# ShieldClock.net
KiCad netlist of a schematic drawn in Altium Designer
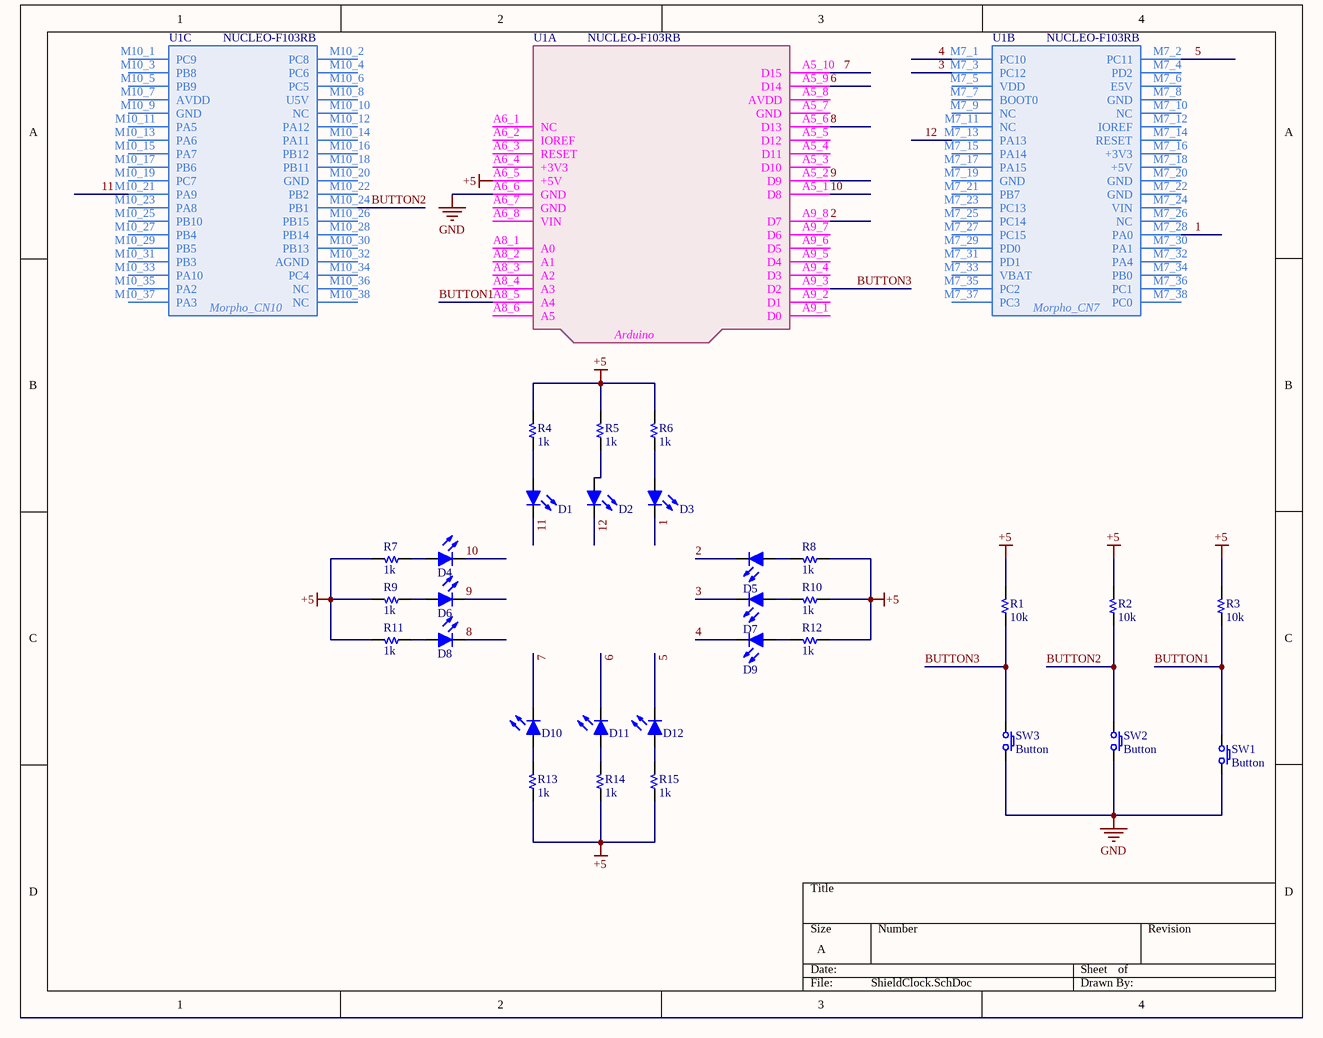
[diagram p0: ShieldClock.SchDoc]

(export (version "E")
  (design (tool "Eeschema 10.0.6"))
  (components
    (comp (ref "D1")
      (value "Led")
      (footprint "LED 3MM - red")
      (description "Typical LED")
      (libsource (lib "chipfc_altium_libs") (part "Led"))
    )
    (comp (ref "D2")
      (value "Led")
      (footprint "LED 3MM - red")
      (description "Typical LED")
      (libsource (lib "chipfc_altium_libs") (part "Led"))
    )
    (comp (ref "D3")
      (value "Led")
      (footprint "LED 3MM - red")
      (description "Typical LED")
      (libsource (lib "chipfc_altium_libs") (part "Led"))
    )
    (comp (ref "D4")
      (value "Led")
      (footprint "LED 3MM - red")
      (description "Typical LED")
      (libsource (lib "chipfc_altium_libs") (part "Led"))
    )
    (comp (ref "D5")
      (value "Led")
      (footprint "LED 3MM - red")
      (description "Typical LED")
      (libsource (lib "chipfc_altium_libs") (part "Led"))
    )
    (comp (ref "D6")
      (value "Led")
      (footprint "LED 3MM - red")
      (description "Typical LED")
      (libsource (lib "chipfc_altium_libs") (part "Led"))
    )
    (comp (ref "D7")
      (value "Led")
      (footprint "LED 3MM - red")
      (description "Typical LED")
      (libsource (lib "chipfc_altium_libs") (part "Led"))
    )
    (comp (ref "D8")
      (value "Led")
      (footprint "LED 3MM - red")
      (description "Typical LED")
      (libsource (lib "chipfc_altium_libs") (part "Led"))
    )
    (comp (ref "D9")
      (value "Led")
      (footprint "LED 3MM - red")
      (description "Typical LED")
      (libsource (lib "chipfc_altium_libs") (part "Led"))
    )
    (comp (ref "D10")
      (value "Led")
      (footprint "LED 3MM - red")
      (description "Typical LED")
      (libsource (lib "chipfc_altium_libs") (part "Led"))
    )
    (comp (ref "D11")
      (value "Led")
      (footprint "LED 3MM - red")
      (description "Typical LED")
      (libsource (lib "chipfc_altium_libs") (part "Led"))
    )
    (comp (ref "D12")
      (value "Led")
      (footprint "LED 3MM - red")
      (description "Typical LED")
      (libsource (lib "chipfc_altium_libs") (part "Led"))
    )
    (comp (ref "R1")
      (value "10k")
      (footprint "R 0805")
      (description "Resistor")
      (libsource (lib "chipfc_altium_libs") (part "Resistor"))
    )
    (comp (ref "R2")
      (value "10k")
      (footprint "R 0805")
      (description "Resistor")
      (libsource (lib "chipfc_altium_libs") (part "Resistor"))
    )
    (comp (ref "R3")
      (value "10k")
      (footprint "R 0805")
      (description "Resistor")
      (libsource (lib "chipfc_altium_libs") (part "Resistor"))
    )
    (comp (ref "R4")
      (value "1k")
      (footprint "R 0805")
      (description "Resistor")
      (libsource (lib "chipfc_altium_libs") (part "Resistor"))
    )
    (comp (ref "R5")
      (value "1k")
      (footprint "R 0805")
      (description "Resistor")
      (libsource (lib "chipfc_altium_libs") (part "Resistor"))
    )
    (comp (ref "R6")
      (value "1k")
      (footprint "R 0805")
      (description "Resistor")
      (libsource (lib "chipfc_altium_libs") (part "Resistor"))
    )
    (comp (ref "R7")
      (value "1k")
      (footprint "R 0805")
      (description "Resistor")
      (libsource (lib "chipfc_altium_libs") (part "Resistor"))
    )
    (comp (ref "R8")
      (value "1k")
      (footprint "R 0805")
      (description "Resistor")
      (libsource (lib "chipfc_altium_libs") (part "Resistor"))
    )
    (comp (ref "R9")
      (value "1k")
      (footprint "R 0805")
      (description "Resistor")
      (libsource (lib "chipfc_altium_libs") (part "Resistor"))
    )
    (comp (ref "R10")
      (value "1k")
      (footprint "R 0805")
      (description "Resistor")
      (libsource (lib "chipfc_altium_libs") (part "Resistor"))
    )
    (comp (ref "R11")
      (value "1k")
      (footprint "R 0805")
      (description "Resistor")
      (libsource (lib "chipfc_altium_libs") (part "Resistor"))
    )
    (comp (ref "R12")
      (value "1k")
      (footprint "R 0805")
      (description "Resistor")
      (libsource (lib "chipfc_altium_libs") (part "Resistor"))
    )
    (comp (ref "R13")
      (value "1k")
      (footprint "R 0805")
      (description "Resistor")
      (libsource (lib "chipfc_altium_libs") (part "Resistor"))
    )
    (comp (ref "R14")
      (value "1k")
      (footprint "R 0805")
      (description "Resistor")
      (libsource (lib "chipfc_altium_libs") (part "Resistor"))
    )
    (comp (ref "R15")
      (value "1k")
      (footprint "R 0805")
      (description "Resistor")
      (libsource (lib "chipfc_altium_libs") (part "Resistor"))
    )
    (comp (ref "SW1")
      (value "Button")
      (footprint "SW/2/DIP")
      (description "Tact switch 2 pin")
      (libsource (lib "chipfc_altium_libs") (part "SW SPST"))
    )
    (comp (ref "SW2")
      (value "Button")
      (footprint "SW/2/DIP")
      (description "Tact switch 2 pin")
      (libsource (lib "chipfc_altium_libs") (part "SW SPST"))
    )
    (comp (ref "SW3")
      (value "Button")
      (footprint "SW/2/DIP")
      (description "Tact switch 2 pin")
      (libsource (lib "chipfc_altium_libs") (part "SW SPST"))
    )
    (comp (ref "U1")
      (value "NUCLEO-F103RB")
      (footprint "NUCLEO")
      (fields (field (name "MANUFACTURER") "STMicroelectronics"))
      (libsource (lib "nucleo") (part "NUCLEO-F103RB"))
    )
  )
  (nets
    (net (code "1") (name "+5") (class "Default")
      (node (ref "R1") (pin "2") (pinfunction "2_2") (pintype "passive"))
      (node (ref "R10") (pin "1") (pinfunction "1_1") (pintype "passive"))
      (node (ref "R11") (pin "2") (pinfunction "2_2") (pintype "passive"))
      (node (ref "R12") (pin "1") (pinfunction "1_1") (pintype "passive"))
      (node (ref "R13") (pin "1") (pinfunction "1_1") (pintype "passive"))
      (node (ref "R14") (pin "1") (pinfunction "1_1") (pintype "passive"))
      (node (ref "R15") (pin "1") (pinfunction "1_1") (pintype "passive"))
      (node (ref "R2") (pin "2") (pinfunction "2_2") (pintype "passive"))
      (node (ref "R3") (pin "2") (pinfunction "2_2") (pintype "passive"))
      (node (ref "R4") (pin "2") (pinfunction "2_2") (pintype "passive"))
      (node (ref "R5") (pin "2") (pinfunction "2_2") (pintype "passive"))
      (node (ref "R6") (pin "2") (pinfunction "2_2") (pintype "passive"))
      (node (ref "R7") (pin "2") (pinfunction "2_2") (pintype "passive"))
      (node (ref "R8") (pin "1") (pinfunction "1_1") (pintype "passive"))
      (node (ref "R9") (pin "2") (pinfunction "2_2") (pintype "passive"))
      (node (ref "U1") (pin "A6_5") (pinfunction "+5V_A6_5") (pintype "passive"))
    )
    (net (code "2") (name "/1") (class "Default")
      (node (ref "D3") (pin "2") (pinfunction "K_2") (pintype "passive"))
      (node (ref "U1") (pin "M7_28") (pinfunction "PA0_M7_28") (pintype "passive"))
    )
    (net (code "3") (name "/2") (class "Default")
      (node (ref "D5") (pin "2") (pinfunction "K_2") (pintype "passive"))
      (node (ref "U1") (pin "A9_8") (pinfunction "D7_A9_8") (pintype "passive"))
    )
    (net (code "4") (name "/3") (class "Default")
      (node (ref "D7") (pin "2") (pinfunction "K_2") (pintype "passive"))
      (node (ref "U1") (pin "M7_3") (pinfunction "PC12_M7_3") (pintype "passive"))
    )
    (net (code "5") (name "/4") (class "Default")
      (node (ref "D9") (pin "2") (pinfunction "K_2") (pintype "passive"))
      (node (ref "U1") (pin "M7_1") (pinfunction "PC10_M7_1") (pintype "passive"))
    )
    (net (code "6") (name "/5") (class "Default")
      (node (ref "D12") (pin "2") (pinfunction "K_2") (pintype "passive"))
      (node (ref "U1") (pin "M7_2") (pinfunction "PC11_M7_2") (pintype "passive"))
    )
    (net (code "7") (name "/6") (class "Default")
      (node (ref "D11") (pin "2") (pinfunction "K_2") (pintype "passive"))
      (node (ref "U1") (pin "A5_9") (pinfunction "D14_A5_9") (pintype "passive"))
    )
    (net (code "8") (name "/7") (class "Default")
      (node (ref "D10") (pin "2") (pinfunction "K_2") (pintype "passive"))
      (node (ref "U1") (pin "A5_10") (pinfunction "D15_A5_10") (pintype "passive"))
    )
    (net (code "9") (name "/8") (class "Default")
      (node (ref "D8") (pin "2") (pinfunction "K_2") (pintype "passive"))
      (node (ref "U1") (pin "A5_6") (pinfunction "D13_A5_6") (pintype "passive"))
    )
    (net (code "10") (name "/9") (class "Default")
      (node (ref "D6") (pin "2") (pinfunction "K_2") (pintype "passive"))
      (node (ref "U1") (pin "A5_2") (pinfunction "D9_A5_2") (pintype "passive"))
    )
    (net (code "11") (name "/10") (class "Default")
      (node (ref "D4") (pin "2") (pinfunction "K_2") (pintype "passive"))
      (node (ref "U1") (pin "A5_1") (pinfunction "D8_A5_1") (pintype "passive"))
    )
    (net (code "12") (name "/11") (class "Default")
      (node (ref "D1") (pin "2") (pinfunction "K_2") (pintype "passive"))
      (node (ref "U1") (pin "M10_21") (pinfunction "PA9_M10_21") (pintype "passive"))
    )
    (net (code "13") (name "/12") (class "Default")
      (node (ref "D2") (pin "2") (pinfunction "K_2") (pintype "passive"))
      (node (ref "U1") (pin "M7_13") (pinfunction "PA13_M7_13") (pintype "passive"))
    )
    (net (code "14") (name "/BUTTON1") (class "Default")
      (node (ref "R3") (pin "1") (pinfunction "1_1") (pintype "passive"))
      (node (ref "SW1") (pin "1") (pinfunction "1_1") (pintype "passive"))
      (node (ref "U1") (pin "A8_5") (pinfunction "A4_A8_5") (pintype "passive"))
    )
    (net (code "15") (name "/BUTTON2") (class "Default")
      (node (ref "R2") (pin "1") (pinfunction "1_1") (pintype "passive"))
      (node (ref "SW2") (pin "1") (pinfunction "1_1") (pintype "passive"))
      (node (ref "U1") (pin "M10_24") (pinfunction "PB1_M10_24") (pintype "passive"))
    )
    (net (code "16") (name "/BUTTON3") (class "Default")
      (node (ref "R1") (pin "1") (pinfunction "1_1") (pintype "passive"))
      (node (ref "SW3") (pin "1") (pinfunction "1_1") (pintype "passive"))
      (node (ref "U1") (pin "A9_3") (pinfunction "D2_A9_3") (pintype "passive"))
    )
    (net (code "17") (name "GND") (class "Default")
      (node (ref "SW1") (pin "2") (pinfunction "2_2") (pintype "passive"))
      (node (ref "SW2") (pin "2") (pinfunction "2_2") (pintype "passive"))
      (node (ref "SW3") (pin "2") (pinfunction "2_2") (pintype "passive"))
      (node (ref "U1") (pin "A6_6") (pinfunction "GND_A6_6") (pintype "passive"))
    )
    (net (code "18") (name "Net-(D1-A)") (class "Default")
      (node (ref "D1") (pin "1") (pinfunction "A_1") (pintype "passive"))
      (node (ref "R4") (pin "1") (pinfunction "1_1") (pintype "passive"))
    )
    (net (code "19") (name "Net-(D2-A)") (class "Default")
      (node (ref "D2") (pin "1") (pinfunction "A_1") (pintype "passive"))
      (node (ref "R5") (pin "1") (pinfunction "1_1") (pintype "passive"))
    )
    (net (code "20") (name "Net-(D3-A)") (class "Default")
      (node (ref "D3") (pin "1") (pinfunction "A_1") (pintype "passive"))
      (node (ref "R6") (pin "1") (pinfunction "1_1") (pintype "passive"))
    )
    (net (code "21") (name "Net-(D4-A)") (class "Default")
      (node (ref "D4") (pin "1") (pinfunction "A_1") (pintype "passive"))
      (node (ref "R7") (pin "1") (pinfunction "1_1") (pintype "passive"))
    )
    (net (code "22") (name "Net-(D5-A)") (class "Default")
      (node (ref "D5") (pin "1") (pinfunction "A_1") (pintype "passive"))
      (node (ref "R8") (pin "2") (pinfunction "2_2") (pintype "passive"))
    )
    (net (code "23") (name "Net-(D6-A)") (class "Default")
      (node (ref "D6") (pin "1") (pinfunction "A_1") (pintype "passive"))
      (node (ref "R9") (pin "1") (pinfunction "1_1") (pintype "passive"))
    )
    (net (code "24") (name "Net-(D7-A)") (class "Default")
      (node (ref "D7") (pin "1") (pinfunction "A_1") (pintype "passive"))
      (node (ref "R10") (pin "2") (pinfunction "2_2") (pintype "passive"))
    )
    (net (code "25") (name "Net-(D8-A)") (class "Default")
      (node (ref "D8") (pin "1") (pinfunction "A_1") (pintype "passive"))
      (node (ref "R11") (pin "1") (pinfunction "1_1") (pintype "passive"))
    )
    (net (code "26") (name "Net-(D9-A)") (class "Default")
      (node (ref "D9") (pin "1") (pinfunction "A_1") (pintype "passive"))
      (node (ref "R12") (pin "2") (pinfunction "2_2") (pintype "passive"))
    )
    (net (code "27") (name "Net-(D10-A)") (class "Default")
      (node (ref "D10") (pin "1") (pinfunction "A_1") (pintype "passive"))
      (node (ref "R13") (pin "2") (pinfunction "2_2") (pintype "passive"))
    )
    (net (code "28") (name "Net-(D11-A)") (class "Default")
      (node (ref "D11") (pin "1") (pinfunction "A_1") (pintype "passive"))
      (node (ref "R14") (pin "2") (pinfunction "2_2") (pintype "passive"))
    )
    (net (code "29") (name "Net-(D12-A)") (class "Default")
      (node (ref "D12") (pin "1") (pinfunction "A_1") (pintype "passive"))
      (node (ref "R15") (pin "2") (pinfunction "2_2") (pintype "passive"))
    )
    (net (code "30") (name "unconnected-(U1A-+3V3-PadA6_4)") (class "Default")
      (node (ref "U1") (pin "A6_4") (pinfunction "+3V3_A6_4") (pintype "passive"))
    )
    (net (code "31") (name "unconnected-(U1A-A0-PadA8_1)") (class "Default")
      (node (ref "U1") (pin "A8_1") (pinfunction "A0_A8_1") (pintype "passive"))
    )
    (net (code "32") (name "unconnected-(U1A-A1-PadA8_2)") (class "Default")
      (node (ref "U1") (pin "A8_2") (pinfunction "A1_A8_2") (pintype "passive"))
    )
    (net (code "33") (name "unconnected-(U1A-A2-PadA8_3)") (class "Default")
      (node (ref "U1") (pin "A8_3") (pinfunction "A2_A8_3") (pintype "passive"))
    )
    (net (code "34") (name "unconnected-(U1A-A3-PadA8_4)") (class "Default")
      (node (ref "U1") (pin "A8_4") (pinfunction "A3_A8_4") (pintype "passive"))
    )
    (net (code "35") (name "unconnected-(U1A-A5-PadA8_6)") (class "Default")
      (node (ref "U1") (pin "A8_6") (pinfunction "A5_A8_6") (pintype "passive"))
    )
    (net (code "36") (name "unconnected-(U1A-AVDD-PadA5_8)") (class "Default")
      (node (ref "U1") (pin "A5_8") (pinfunction "AVDD_A5_8") (pintype "passive"))
    )
    (net (code "37") (name "unconnected-(U1A-D0-PadA9_1)") (class "Default")
      (node (ref "U1") (pin "A9_1") (pinfunction "D0_A9_1") (pintype "passive"))
    )
    (net (code "38") (name "unconnected-(U1A-D1-PadA9_2)") (class "Default")
      (node (ref "U1") (pin "A9_2") (pinfunction "D1_A9_2") (pintype "passive"))
    )
    (net (code "39") (name "unconnected-(U1A-D3-PadA9_4)") (class "Default")
      (node (ref "U1") (pin "A9_4") (pinfunction "D3_A9_4") (pintype "passive"))
    )
    (net (code "40") (name "unconnected-(U1A-D4-PadA9_5)") (class "Default")
      (node (ref "U1") (pin "A9_5") (pinfunction "D4_A9_5") (pintype "passive"))
    )
    (net (code "41") (name "unconnected-(U1A-D5-PadA9_6)") (class "Default")
      (node (ref "U1") (pin "A9_6") (pinfunction "D5_A9_6") (pintype "passive"))
    )
    (net (code "42") (name "unconnected-(U1A-D6-PadA9_7)") (class "Default")
      (node (ref "U1") (pin "A9_7") (pinfunction "D6_A9_7") (pintype "passive"))
    )
    (net (code "43") (name "unconnected-(U1A-D10-PadA5_3)") (class "Default")
      (node (ref "U1") (pin "A5_3") (pinfunction "D10_A5_3") (pintype "passive"))
    )
    (net (code "44") (name "unconnected-(U1A-D11-PadA5_4)") (class "Default")
      (node (ref "U1") (pin "A5_4") (pinfunction "D11_A5_4") (pintype "passive"))
    )
    (net (code "45") (name "unconnected-(U1A-D12-PadA5_5)") (class "Default")
      (node (ref "U1") (pin "A5_5") (pinfunction "D12_A5_5") (pintype "passive"))
    )
    (net (code "46") (name "unconnected-(U1A-GND-PadA5_7)") (class "Default")
      (node (ref "U1") (pin "A5_7") (pinfunction "GND_A5_7") (pintype "passive"))
    )
    (net (code "47") (name "unconnected-(U1A-GND-PadA6_7)") (class "Default")
      (node (ref "U1") (pin "A6_7") (pinfunction "GND_A6_7") (pintype "passive"))
    )
    (net (code "48") (name "unconnected-(U1A-IOREF-PadA6_2)") (class "Default")
      (node (ref "U1") (pin "A6_2") (pinfunction "IOREF_A6_2") (pintype "passive"))
    )
    (net (code "49") (name "unconnected-(U1A-NC-PadA6_1)") (class "Default")
      (node (ref "U1") (pin "A6_1") (pinfunction "NC_A6_1") (pintype "passive"))
    )
    (net (code "50") (name "unconnected-(U1A-RESET-PadA6_3)") (class "Default")
      (node (ref "U1") (pin "A6_3") (pinfunction "RESET_A6_3") (pintype "passive"))
    )
    (net (code "51") (name "unconnected-(U1A-VIN-PadA6_8)") (class "Default")
      (node (ref "U1") (pin "A6_8") (pinfunction "VIN_A6_8") (pintype "passive"))
    )
    (net (code "52") (name "unconnected-(U1B-+3V3-PadM7_16)") (class "Default")
      (node (ref "U1") (pin "M7_16") (pinfunction "+3V3_M7_16") (pintype "passive"))
    )
    (net (code "53") (name "unconnected-(U1B-+5V-PadM7_18)") (class "Default")
      (node (ref "U1") (pin "M7_18") (pinfunction "+5V_M7_18") (pintype "passive"))
    )
    (net (code "54") (name "unconnected-(U1B-BOOT0-PadM7_7)") (class "Default")
      (node (ref "U1") (pin "M7_7") (pinfunction "BOOT0_M7_7") (pintype "passive"))
    )
    (net (code "55") (name "unconnected-(U1B-E5V-PadM7_6)") (class "Default")
      (node (ref "U1") (pin "M7_6") (pinfunction "E5V_M7_6") (pintype "passive"))
    )
    (net (code "56") (name "unconnected-(U1B-GND-PadM7_8)") (class "Default")
      (node (ref "U1") (pin "M7_8") (pinfunction "GND_M7_8") (pintype "passive"))
    )
    (net (code "57") (name "unconnected-(U1B-GND-PadM7_19)") (class "Default")
      (node (ref "U1") (pin "M7_19") (pinfunction "GND_M7_19") (pintype "passive"))
    )
    (net (code "58") (name "unconnected-(U1B-GND-PadM7_20)") (class "Default")
      (node (ref "U1") (pin "M7_20") (pinfunction "GND_M7_20") (pintype "passive"))
    )
    (net (code "59") (name "unconnected-(U1B-GND-PadM7_22)") (class "Default")
      (node (ref "U1") (pin "M7_22") (pinfunction "GND_M7_22") (pintype "passive"))
    )
    (net (code "60") (name "unconnected-(U1B-IOREF-PadM7_12)") (class "Default")
      (node (ref "U1") (pin "M7_12") (pinfunction "IOREF_M7_12") (pintype "passive"))
    )
    (net (code "61") (name "unconnected-(U1B-NC-PadM7_9)") (class "Default")
      (node (ref "U1") (pin "M7_9") (pinfunction "NC_M7_9") (pintype "passive"))
    )
    (net (code "62") (name "unconnected-(U1B-NC-PadM7_10)") (class "Default")
      (node (ref "U1") (pin "M7_10") (pinfunction "NC_M7_10") (pintype "passive"))
    )
    (net (code "63") (name "unconnected-(U1B-NC-PadM7_11)") (class "Default")
      (node (ref "U1") (pin "M7_11") (pinfunction "NC_M7_11") (pintype "passive"))
    )
    (net (code "64") (name "unconnected-(U1B-NC-PadM7_26)") (class "Default")
      (node (ref "U1") (pin "M7_26") (pinfunction "NC_M7_26") (pintype "passive"))
    )
    (net (code "65") (name "unconnected-(U1B-PA1-PadM7_30)") (class "Default")
      (node (ref "U1") (pin "M7_30") (pinfunction "PA1_M7_30") (pintype "passive"))
    )
    (net (code "66") (name "unconnected-(U1B-PA4-PadM7_32)") (class "Default")
      (node (ref "U1") (pin "M7_32") (pinfunction "PA4_M7_32") (pintype "passive"))
    )
    (net (code "67") (name "unconnected-(U1B-PA14-PadM7_15)") (class "Default")
      (node (ref "U1") (pin "M7_15") (pinfunction "PA14_M7_15") (pintype "passive"))
    )
    (net (code "68") (name "unconnected-(U1B-PA15-PadM7_17)") (class "Default")
      (node (ref "U1") (pin "M7_17") (pinfunction "PA15_M7_17") (pintype "passive"))
    )
    (net (code "69") (name "unconnected-(U1B-PB0-PadM7_34)") (class "Default")
      (node (ref "U1") (pin "M7_34") (pinfunction "PB0_M7_34") (pintype "passive"))
    )
    (net (code "70") (name "unconnected-(U1B-PB7-PadM7_21)") (class "Default")
      (node (ref "U1") (pin "M7_21") (pinfunction "PB7_M7_21") (pintype "passive"))
    )
    (net (code "71") (name "unconnected-(U1B-PC0-PadM7_38)") (class "Default")
      (node (ref "U1") (pin "M7_38") (pinfunction "PC0_M7_38") (pintype "passive"))
    )
    (net (code "72") (name "unconnected-(U1B-PC1-PadM7_36)") (class "Default")
      (node (ref "U1") (pin "M7_36") (pinfunction "PC1_M7_36") (pintype "passive"))
    )
    (net (code "73") (name "unconnected-(U1B-PC2-PadM7_35)") (class "Default")
      (node (ref "U1") (pin "M7_35") (pinfunction "PC2_M7_35") (pintype "passive"))
    )
    (net (code "74") (name "unconnected-(U1B-PC3-PadM7_37)") (class "Default")
      (node (ref "U1") (pin "M7_37") (pinfunction "PC3_M7_37") (pintype "passive"))
    )
    (net (code "75") (name "unconnected-(U1B-PC13-PadM7_23)") (class "Default")
      (node (ref "U1") (pin "M7_23") (pinfunction "PC13_M7_23") (pintype "passive"))
    )
    (net (code "76") (name "unconnected-(U1B-PC14-PadM7_25)") (class "Default")
      (node (ref "U1") (pin "M7_25") (pinfunction "PC14_M7_25") (pintype "passive"))
    )
    (net (code "77") (name "unconnected-(U1B-PC15-PadM7_27)") (class "Default")
      (node (ref "U1") (pin "M7_27") (pinfunction "PC15_M7_27") (pintype "passive"))
    )
    (net (code "78") (name "unconnected-(U1B-PD0-PadM7_29)") (class "Default")
      (node (ref "U1") (pin "M7_29") (pinfunction "PD0_M7_29") (pintype "passive"))
    )
    (net (code "79") (name "unconnected-(U1B-PD1-PadM7_31)") (class "Default")
      (node (ref "U1") (pin "M7_31") (pinfunction "PD1_M7_31") (pintype "passive"))
    )
    (net (code "80") (name "unconnected-(U1B-PD2-PadM7_4)") (class "Default")
      (node (ref "U1") (pin "M7_4") (pinfunction "PD2_M7_4") (pintype "passive"))
    )
    (net (code "81") (name "unconnected-(U1B-RESET-PadM7_14)") (class "Default")
      (node (ref "U1") (pin "M7_14") (pinfunction "RESET_M7_14") (pintype "passive"))
    )
    (net (code "82") (name "unconnected-(U1B-VBAT-PadM7_33)") (class "Default")
      (node (ref "U1") (pin "M7_33") (pinfunction "VBAT_M7_33") (pintype "passive"))
    )
    (net (code "83") (name "unconnected-(U1B-VDD-PadM7_5)") (class "Default")
      (node (ref "U1") (pin "M7_5") (pinfunction "VDD_M7_5") (pintype "passive"))
    )
    (net (code "84") (name "unconnected-(U1B-VIN-PadM7_24)") (class "Default")
      (node (ref "U1") (pin "M7_24") (pinfunction "VIN_M7_24") (pintype "passive"))
    )
    (net (code "85") (name "unconnected-(U1C-AGND-PadM10_32)") (class "Default")
      (node (ref "U1") (pin "M10_32") (pinfunction "AGND_M10_32") (pintype "passive"))
    )
    (net (code "86") (name "unconnected-(U1C-AVDD-PadM10_7)") (class "Default")
      (node (ref "U1") (pin "M10_7") (pinfunction "AVDD_M10_7") (pintype "passive"))
    )
    (net (code "87") (name "unconnected-(U1C-GND-PadM10_9)") (class "Default")
      (node (ref "U1") (pin "M10_9") (pinfunction "GND_M10_9") (pintype "passive"))
    )
    (net (code "88") (name "unconnected-(U1C-GND-PadM10_20)") (class "Default")
      (node (ref "U1") (pin "M10_20") (pinfunction "GND_M10_20") (pintype "passive"))
    )
    (net (code "89") (name "unconnected-(U1C-NC-PadM10_10)") (class "Default")
      (node (ref "U1") (pin "M10_10") (pinfunction "NC_M10_10") (pintype "passive"))
    )
    (net (code "90") (name "unconnected-(U1C-NC-PadM10_36)") (class "Default")
      (node (ref "U1") (pin "M10_36") (pinfunction "NC_M10_36") (pintype "passive"))
    )
    (net (code "91") (name "unconnected-(U1C-NC-PadM10_38)") (class "Default")
      (node (ref "U1") (pin "M10_38") (pinfunction "NC_M10_38") (pintype "passive"))
    )
    (net (code "92") (name "unconnected-(U1C-PA2-PadM10_35)") (class "Default")
      (node (ref "U1") (pin "M10_35") (pinfunction "PA2_M10_35") (pintype "passive"))
    )
    (net (code "93") (name "unconnected-(U1C-PA3-PadM10_37)") (class "Default")
      (node (ref "U1") (pin "M10_37") (pinfunction "PA3_M10_37") (pintype "passive"))
    )
    (net (code "94") (name "unconnected-(U1C-PA5-PadM10_11)") (class "Default")
      (node (ref "U1") (pin "M10_11") (pinfunction "PA5_M10_11") (pintype "passive"))
    )
    (net (code "95") (name "unconnected-(U1C-PA6-PadM10_13)") (class "Default")
      (node (ref "U1") (pin "M10_13") (pinfunction "PA6_M10_13") (pintype "passive"))
    )
    (net (code "96") (name "unconnected-(U1C-PA7-PadM10_15)") (class "Default")
      (node (ref "U1") (pin "M10_15") (pinfunction "PA7_M10_15") (pintype "passive"))
    )
    (net (code "97") (name "unconnected-(U1C-PA8-PadM10_23)") (class "Default")
      (node (ref "U1") (pin "M10_23") (pinfunction "PA8_M10_23") (pintype "passive"))
    )
    (net (code "98") (name "unconnected-(U1C-PA10-PadM10_33)") (class "Default")
      (node (ref "U1") (pin "M10_33") (pinfunction "PA10_M10_33") (pintype "passive"))
    )
    (net (code "99") (name "unconnected-(U1C-PA11-PadM10_14)") (class "Default")
      (node (ref "U1") (pin "M10_14") (pinfunction "PA11_M10_14") (pintype "passive"))
    )
    (net (code "100") (name "unconnected-(U1C-PA12-PadM10_12)") (class "Default")
      (node (ref "U1") (pin "M10_12") (pinfunction "PA12_M10_12") (pintype "passive"))
    )
    (net (code "101") (name "unconnected-(U1C-PB2-PadM10_22)") (class "Default")
      (node (ref "U1") (pin "M10_22") (pinfunction "PB2_M10_22") (pintype "passive"))
    )
    (net (code "102") (name "unconnected-(U1C-PB3-PadM10_31)") (class "Default")
      (node (ref "U1") (pin "M10_31") (pinfunction "PB3_M10_31") (pintype "passive"))
    )
    (net (code "103") (name "unconnected-(U1C-PB4-PadM10_27)") (class "Default")
      (node (ref "U1") (pin "M10_27") (pinfunction "PB4_M10_27") (pintype "passive"))
    )
    (net (code "104") (name "unconnected-(U1C-PB5-PadM10_29)") (class "Default")
      (node (ref "U1") (pin "M10_29") (pinfunction "PB5_M10_29") (pintype "passive"))
    )
    (net (code "105") (name "unconnected-(U1C-PB6-PadM10_17)") (class "Default")
      (node (ref "U1") (pin "M10_17") (pinfunction "PB6_M10_17") (pintype "passive"))
    )
    (net (code "106") (name "unconnected-(U1C-PB8-PadM10_3)") (class "Default")
      (node (ref "U1") (pin "M10_3") (pinfunction "PB8_M10_3") (pintype "passive"))
    )
    (net (code "107") (name "unconnected-(U1C-PB9-PadM10_5)") (class "Default")
      (node (ref "U1") (pin "M10_5") (pinfunction "PB9_M10_5") (pintype "passive"))
    )
    (net (code "108") (name "unconnected-(U1C-PB10-PadM10_25)") (class "Default")
      (node (ref "U1") (pin "M10_25") (pinfunction "PB10_M10_25") (pintype "passive"))
    )
    (net (code "109") (name "unconnected-(U1C-PB11-PadM10_18)") (class "Default")
      (node (ref "U1") (pin "M10_18") (pinfunction "PB11_M10_18") (pintype "passive"))
    )
    (net (code "110") (name "unconnected-(U1C-PB12-PadM10_16)") (class "Default")
      (node (ref "U1") (pin "M10_16") (pinfunction "PB12_M10_16") (pintype "passive"))
    )
    (net (code "111") (name "unconnected-(U1C-PB13-PadM10_30)") (class "Default")
      (node (ref "U1") (pin "M10_30") (pinfunction "PB13_M10_30") (pintype "passive"))
    )
    (net (code "112") (name "unconnected-(U1C-PB14-PadM10_28)") (class "Default")
      (node (ref "U1") (pin "M10_28") (pinfunction "PB14_M10_28") (pintype "passive"))
    )
    (net (code "113") (name "unconnected-(U1C-PB15-PadM10_26)") (class "Default")
      (node (ref "U1") (pin "M10_26") (pinfunction "PB15_M10_26") (pintype "passive"))
    )
    (net (code "114") (name "unconnected-(U1C-PC4-PadM10_34)") (class "Default")
      (node (ref "U1") (pin "M10_34") (pinfunction "PC4_M10_34") (pintype "passive"))
    )
    (net (code "115") (name "unconnected-(U1C-PC5-PadM10_6)") (class "Default")
      (node (ref "U1") (pin "M10_6") (pinfunction "PC5_M10_6") (pintype "passive"))
    )
    (net (code "116") (name "unconnected-(U1C-PC6-PadM10_4)") (class "Default")
      (node (ref "U1") (pin "M10_4") (pinfunction "PC6_M10_4") (pintype "passive"))
    )
    (net (code "117") (name "unconnected-(U1C-PC7-PadM10_19)") (class "Default")
      (node (ref "U1") (pin "M10_19") (pinfunction "PC7_M10_19") (pintype "passive"))
    )
    (net (code "118") (name "unconnected-(U1C-PC8-PadM10_2)") (class "Default")
      (node (ref "U1") (pin "M10_2") (pinfunction "PC8_M10_2") (pintype "passive"))
    )
    (net (code "119") (name "unconnected-(U1C-PC9-PadM10_1)") (class "Default")
      (node (ref "U1") (pin "M10_1") (pinfunction "PC9_M10_1") (pintype "passive"))
    )
    (net (code "120") (name "unconnected-(U1C-U5V-PadM10_8)") (class "Default")
      (node (ref "U1") (pin "M10_8") (pinfunction "U5V_M10_8") (pintype "passive"))
    )
  )
)
